# 4_Sensors.net
KiCad netlist of a schematic drawn in Altium Designer
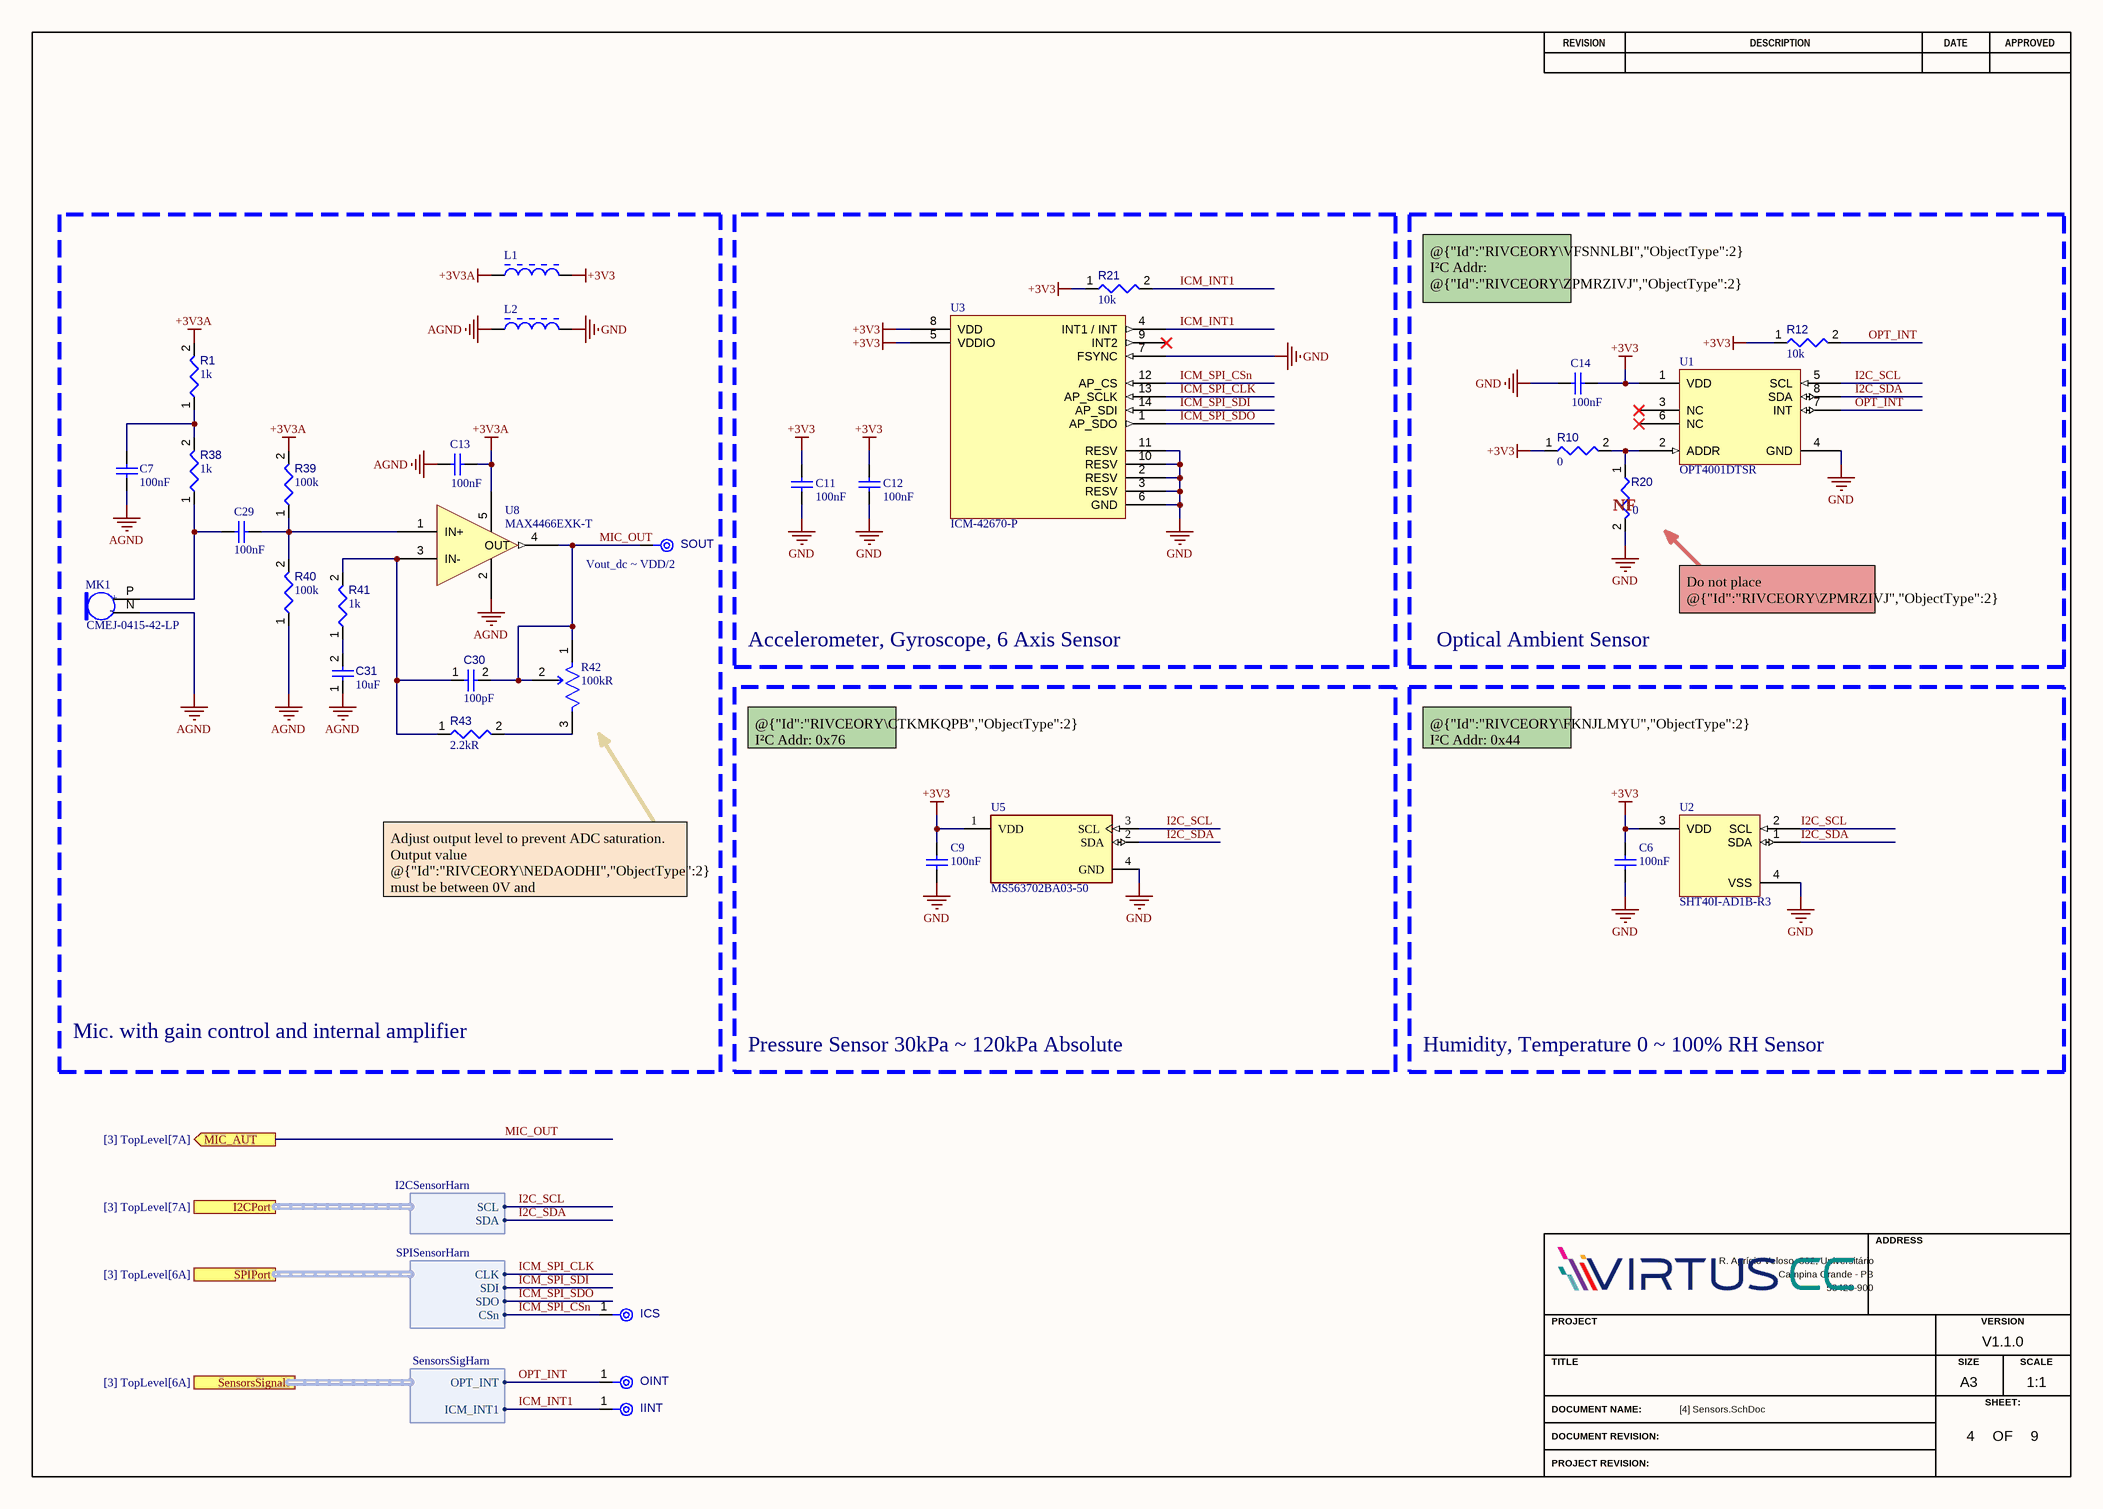
[diagram p0: [4] Sensors.SchDoc]

(export (version "E")
  (design (tool "Eeschema 10.0.6"))
  (components
    (comp (ref "C6")
      (value "100nF")
      (footprint "CAPC0603(1608)100_L")
      (description "Multilayer Ceramic Capacitor, 0.1 uF, 16 V, ± 20%, X7R, 0603 [1608 Metric]")
      (fields (field (name "TOLERANCE") "20%") (field (name "Comment") "VJ0603Y104MXJCW1BC"))
      (libsource (lib "UFCG - Universidade Federal de Campina Grande") (part "CAP"))
    )
    (comp (ref "C7")
      (value "100nF")
      (footprint "CAPC0603(1608)100_L")
      (description "Multilayer Ceramic Capacitor, 0.1 uF, 16 V, ± 20%, X7R, 0603 [1608 Metric]")
      (fields (field (name "TOLERANCE") "20%") (field (name "Comment") "VJ0603Y104MXJCW1BC"))
      (libsource (lib "UFCG - Universidade Federal de Campina Grande") (part "CAP"))
    )
    (comp (ref "C9")
      (value "100nF")
      (footprint "CAPC0603(1608)100_L")
      (description "Multilayer Ceramic Capacitor, 0.1 uF, 16 V, ± 20%, X7R, 0603 [1608 Metric]")
      (fields (field (name "TOLERANCE") "20%") (field (name "Comment") "VJ0603Y104MXJCW1BC"))
      (libsource (lib "UFCG - Universidade Federal de Campina Grande") (part "CAP"))
    )
    (comp (ref "C11")
      (value "100nF")
      (footprint "CAPC0603(1608)100_L")
      (description "Multilayer Ceramic Capacitor, 0.1 uF, 16 V, ± 20%, X7R, 0603 [1608 Metric]")
      (fields (field (name "TOLERANCE") "20%") (field (name "Comment") "VJ0603Y104MXJCW1BC"))
      (libsource (lib "UFCG - Universidade Federal de Campina Grande") (part "CAP"))
    )
    (comp (ref "C12")
      (value "100nF")
      (footprint "CAPC0603(1608)100_L")
      (description "Multilayer Ceramic Capacitor, 0.1 uF, 16 V, ± 20%, X7R, 0603 [1608 Metric]")
      (fields (field (name "TOLERANCE") "20%") (field (name "Comment") "VJ0603Y104MXJCW1BC"))
      (libsource (lib "UFCG - Universidade Federal de Campina Grande") (part "CAP"))
    )
    (comp (ref "C13")
      (value "100nF")
      (footprint "CAPC0603(1608)100_L")
      (description "Multilayer Ceramic Capacitor, 0.1 uF, 16 V, ± 20%, X7R, 0603 [1608 Metric]")
      (fields (field (name "TOLERANCE") "20%") (field (name "Comment") "VJ0603Y104MXJCW1BC"))
      (libsource (lib "UFCG - Universidade Federal de Campina Grande") (part "CAP"))
    )
    (comp (ref "C14")
      (value "100nF")
      (footprint "CAPC0603(1608)100_L")
      (description "Multilayer Ceramic Capacitor, 0.1 uF, 16 V, ± 20%, X7R, 0603 [1608 Metric]")
      (fields (field (name "TOLERANCE") "20%") (field (name "Comment") "VJ0603Y104MXJCW1BC"))
      (libsource (lib "UFCG - Universidade Federal de Campina Grande") (part "CAP"))
    )
    (comp (ref "C29")
      (value "100nF")
      (footprint "CAPC0603(1608)100_L")
      (description "Multilayer Ceramic Capacitor, 0.1 uF, 16 V, ± 20%, X7R, 0603 [1608 Metric]")
      (fields (field (name "TOLERANCE") "20%") (field (name "Comment") "VJ0603Y104MXJCW1BC"))
      (libsource (lib "UFCG - Universidade Federal de Campina Grande") (part "CAP"))
    )
    (comp (ref "C30")
      (value "100pF")
      (footprint "CAPC0603(1608)100_L")
      (description "Multilayer Ceramic Capacitor, 100 pF, 50 V, ï¿½ 10%, C0G (NP0), 0603 [1608 Metric]")
      (fields (field (name "TOLERANCE") "10%") (field (name "Comment") "C0603C101K5GACTU"))
      (libsource (lib "UFCG - Universidade Federal de Campina Grande") (part "CAP-NP-2"))
    )
    (comp (ref "C31")
      (value "10uF")
      (footprint "CAPC0603(1608)100_L")
      (description "Multilayer Ceramic Capacitor, 10 uF, 6.3 V, ± 20%, X5R, 0603 [1608 Metric]")
      (fields (field (name "TOLERANCE") "20%") (field (name "Comment") "GRM188R60J106ME47D"))
      (libsource (lib "UFCG - Universidade Federal de Campina Grande") (part "CAP-NP-2"))
    )
    (comp (ref "ICS")
      (value "TPAD6R")
      (footprint "TP06R")
      (description "0.6mm round")
      (libsource (lib "UFCG - Universidade Federal de Campina Grande") (part "CMP-001-0001-4"))
    )
    (comp (ref "IINT")
      (value "TPAD6R")
      (footprint "TP06R")
      (description "0.6mm round")
      (libsource (lib "UFCG - Universidade Federal de Campina Grande") (part "CMP-001-0001-4"))
    )
    (comp (ref "L1")
      (value "BLM21PG331SN1D")
      (footprint "INDC2013X105X50ML20T20")
      (fields (field (name "TOLERANCE") "25%") (field (name "MANUFACTURER") "Murata"))
      (libsource (lib "UFCG - Universidade Federal de Campina Grande") (part "IND-FB-2"))
    )
    (comp (ref "L2")
      (value "BLM21PG331SN1D")
      (footprint "INDC2013X105X50ML20T20")
      (fields (field (name "TOLERANCE") "25%") (field (name "MANUFACTURER") "Murata"))
      (libsource (lib "UFCG - Universidade Federal de Campina Grande") (part "IND-FB-2"))
    )
    (comp (ref "MK1")
      (value "CMEJ-0415-42-LP")
      (footprint "MIC_CMEJ-0415-42-LP")
      (description "4.0 mm, Omnidirectional, PCB Mount, 2.0 Vdc, Elecret Condenser Microphone")
      (fields (field (name "MF") "{'manufacturer': u'CUI'}"))
      (libsource (lib "UFCG - Universidade Federal de Campina Grande") (part "CMEJ-0415-42-LP"))
    )
    (comp (ref "OINT")
      (value "TPAD6R")
      (footprint "TP06R")
      (description "0.6mm round")
      (libsource (lib "UFCG - Universidade Federal de Campina Grande") (part "CMP-001-0001-4"))
    )
    (comp (ref "R1")
      (value "1k")
      (footprint "RESC0603(1608)_L")
      (description "Chip Resistor, 1 KOhm, +/-1%, 0.1 W, -55 to 155 degC, 0603 (1608 Metric)")
      (fields (field (name "POWER") "100mW") (field (name "TOLERANCE") "1%"))
      (libsource (lib "UFCG - Universidade Federal de Campina Grande") (part "RES-2"))
    )
    (comp (ref "R10")
      (value "0")
      (footprint "RESC0603(1608)_L")
      (description "Chip Resistor, 0 Ohm, 0.1 W, -55 to 155 degC, 0603 (1608 Metric)")
      (fields (field (name "TOLERANCE") "5%") (field (name "POWER") "100mW"))
      (libsource (lib "UFCG - Universidade Federal de Campina Grande") (part "RES-2"))
    )
    (comp (ref "R12")
      (value "10k")
      (footprint "RESC0603(1608)_L")
      (description "Chip Resistor, 10 KOhm, +/- 1%, 01 W, -55 to 155 degC, 0603 (1608 Metric)")
      (fields (field (name "POWER") "100mW") (field (name "TOLERANCE") "1%"))
      (libsource (lib "UFCG - Universidade Federal de Campina Grande") (part "RES-2"))
    )
    (comp (ref "R20")
      (value "0")
      (footprint "RESC0603(1608)_L")
      (description "Chip Resistor, 0 Ohm, 0.1 W, -55 to 155 degC, 0603 (1608 Metric)")
      (fields (field (name "TOLERANCE") "5%") (field (name "POWER") "100mW"))
      (libsource (lib "UFCG - Universidade Federal de Campina Grande") (part "RES-2"))
    )
    (comp (ref "R21")
      (value "10k")
      (footprint "RESC0603(1608)_L")
      (description "Chip Resistor, 10 KOhm, +/- 1%, 01 W, -55 to 155 degC, 0603 (1608 Metric)")
      (fields (field (name "POWER") "100mW") (field (name "TOLERANCE") "1%"))
      (libsource (lib "UFCG - Universidade Federal de Campina Grande") (part "RES-2"))
    )
    (comp (ref "R38")
      (value "1k")
      (footprint "RESC0603(1608)_L")
      (description "Chip Resistor, 1 KOhm, +/-1%, 0.1 W, -55 to 155 degC, 0603 (1608 Metric)")
      (fields (field (name "POWER") "100mW") (field (name "TOLERANCE") "1%"))
      (libsource (lib "UFCG - Universidade Federal de Campina Grande") (part "RES-2"))
    )
    (comp (ref "R39")
      (value "100k")
      (footprint "RESC0603(1608)_L")
      (description "Chip Resistor, 100 KOhm, +/- 1%, 0.1 W, -55 to 155 degC, 0603 (1608 Metric)")
      (fields (field (name "TOLERANCE") "1%") (field (name "POWER") "100mW"))
      (libsource (lib "UFCG - Universidade Federal de Campina Grande") (part "RES-2"))
    )
    (comp (ref "R40")
      (value "100k")
      (footprint "RESC0603(1608)_L")
      (description "Chip Resistor, 100 KOhm, +/- 1%, 0.1 W, -55 to 155 degC, 0603 (1608 Metric)")
      (fields (field (name "TOLERANCE") "1%") (field (name "POWER") "100mW"))
      (libsource (lib "UFCG - Universidade Federal de Campina Grande") (part "RES-2"))
    )
    (comp (ref "R41")
      (value "1k")
      (footprint "RESC0603(1608)_L")
      (description "Chip Resistor, 1 KOhm, +/-1%, 0.1 W, -55 to 155 degC, 0603 (1608 Metric)")
      (fields (field (name "POWER") "100mW") (field (name "TOLERANCE") "1%"))
      (libsource (lib "UFCG - Universidade Federal de Campina Grande") (part "RES-2"))
    )
    (comp (ref "R42")
      (value "100kR")
      (footprint "FP-TC33X-2-MFG")
      (description "Cermet trimmer potentiometer, 100 kΩ, 0.1 W, SMD, on top, TC33X-2-104E")
      (fields (field (name "TOLERANCE") "25%") (field (name "Comment") "TC33X-2-104E"))
      (libsource (lib "UFCG - Universidade Federal de Campina Grande") (part "13357d81287629c2fd191d242cfa50c"))
    )
    (comp (ref "R43")
      (value "2.2kR")
      (footprint "RESC0603(1608)_L")
      (description "SMD Chip Resistor, 2.2 kOhm, ± 1%, 100 mW, 0603 [1608 Metric], Thick Film, General Purpose")
      (fields (field (name "TOLERANCE") "1%") (field (name "Comment") "CRCW06032K20FKEA"))
      (libsource (lib "UFCG - Universidade Federal de Campina Grande") (part "RES-2"))
    )
    (comp (ref "SOUT")
      (value "TPAD6R")
      (footprint "TP06R")
      (description "0.6mm round")
      (libsource (lib "") (part "CMP-001-0001-4_1"))
    )
    (comp (ref "U1")
      (value "OPT4001DTSR")
      (footprint "SON50P130X60-8N")
      (description "High-speed high-precision digital ambient light sensor (ALS) 8-SOT-5X3 -40 to 85")
      (libsource (lib "UFCG - Universidade Federal de Campina Grande") (part "New symbol 1"))
    )
    (comp (ref "U2")
      (value "SHT40I-AD1B-R3")
      (footprint "QFN80P150X150X55-4N")
      (description "Humidity And Temperature Sensor")
      (libsource (lib "UFCG - Universidade Federal de Campina Grande") (part "SHT40I-AD1B-R3"))
    )
    (comp (ref "U3")
      (value "ICM-42670-P")
      (footprint "QFN50P300X250X81-14N")
      (description "Mems Module, 1.71-3.6 V, Lga-14 Rohs Compliant: Yes")
      (libsource (lib "UFCG - Universidade Federal de Campina Grande") (part "ICM-42670-P"))
    )
    (comp (ref "U5")
      (value "MS563702BA03-50")
      (footprint "FP-MS563702BA03-50-MFG")
      (description "Pressure Sensor, Barometric, 300 mbar, 1200 mbar, QFN, 8, -40 C")
      (libsource (lib "UFCG - Universidade Federal de Campina Grande") (part "74709a9a55dd6d6ee219151e6d8b12f"))
    )
    (comp (ref "U8")
      (value "MAX4466EXK-T")
      (footprint "SOT65P200X110-5N")
      (description "Audio Amp Microphone 1-CH Mono Class-AB 5-Pin SC-70 T/R")
      (libsource (lib "UFCG - Universidade Federal de Campina Grande") (part "MAX4466EXK-T"))
    )
  )
  (nets
    (net (code "4") (name "+3V3") (class "Default")
      (node (ref "C11") (pin "2") (pinfunction "2_2") (pintype "passive"))
      (node (ref "C12") (pin "2") (pinfunction "2_2") (pintype "passive"))
      (node (ref "C14") (pin "1") (pinfunction "1_1") (pintype "passive"))
      (node (ref "C6") (pin "1") (pinfunction "1_1") (pintype "passive"))
      (node (ref "C9") (pin "1") (pinfunction "1_1") (pintype "passive"))
      (node (ref "L1") (pin "2") (pinfunction "2_2") (pintype "passive"))
      (node (ref "R10") (pin "1") (pinfunction "1_1") (pintype "passive"))
      (node (ref "R12") (pin "1") (pinfunction "1_1") (pintype "passive"))
      (node (ref "R21") (pin "1") (pinfunction "1_1") (pintype "passive"))
      (node (ref "U1") (pin "1") (pinfunction "VDD_1") (pintype "power_in"))
      (node (ref "U2") (pin "3") (pinfunction "VDD_3") (pintype "power_in"))
      (node (ref "U3") (pin "5") (pinfunction "VDDIO_5") (pintype "power_in"))
      (node (ref "U3") (pin "8") (pinfunction "VDD_8") (pintype "power_in"))
      (node (ref "U5") (pin "1") (pinfunction "VDD_1") (pintype "power_in"))
    )
    (net (code "5") (name "+3V3A") (class "Default")
      (node (ref "C13") (pin "1") (pinfunction "1_1") (pintype "passive"))
      (node (ref "L1") (pin "1") (pinfunction "1_1") (pintype "passive"))
      (node (ref "R1") (pin "2") (pinfunction "2_2") (pintype "passive"))
      (node (ref "R39") (pin "2") (pinfunction "2_2") (pintype "passive"))
      (node (ref "U8") (pin "5") (pinfunction "VCC_5") (pintype "power_in"))
    )
    (net (code "6") (name "/I2C_SCL") (class "Default")
      (node (ref "U1") (pin "5") (pinfunction "SCL_5") (pintype "input"))
      (node (ref "U2") (pin "2") (pinfunction "SCL_2") (pintype "input"))
      (node (ref "U5") (pin "3") (pinfunction "SCL_3") (pintype "input"))
    )
    (net (code "7") (name "/I2C_SDA") (class "Default")
      (node (ref "U1") (pin "8") (pinfunction "SDA_8") (pintype "bidirectional"))
      (node (ref "U2") (pin "1") (pinfunction "SDA_1") (pintype "bidirectional"))
      (node (ref "U5") (pin "2") (pinfunction "SDA_2") (pintype "bidirectional"))
    )
    (net (code "8") (name "/ICM_INT1") (class "Default")
      (node (ref "IINT") (pin "1") (pinfunction "TP_1") (pintype "passive"))
      (node (ref "R21") (pin "2") (pinfunction "2_2") (pintype "passive"))
      (node (ref "U3") (pin "4") (pinfunction "INT1_/_INT_4") (pintype "output"))
    )
    (net (code "9") (name "/ICM_SPI_CLK") (class "Default")
      (node (ref "U3") (pin "13") (pinfunction "AP_SCLK_13") (pintype "input"))
    )
    (net (code "10") (name "/ICM_SPI_CSn") (class "Default")
      (node (ref "ICS") (pin "1") (pinfunction "TP_1") (pintype "passive"))
      (node (ref "U3") (pin "12") (pinfunction "AP_CS_12") (pintype "input"))
    )
    (net (code "11") (name "/ICM_SPI_SDI") (class "Default")
      (node (ref "U3") (pin "14") (pinfunction "AP_SDI_14") (pintype "input"))
    )
    (net (code "12") (name "/ICM_SPI_SDO") (class "Default")
      (node (ref "U3") (pin "1") (pinfunction "AP_SDO_1") (pintype "output"))
    )
    (net (code "13") (name "/MIC_OUT") (class "Default")
      (node (ref "C30") (pin "2") (pinfunction "2_2") (pintype "passive"))
      (node (ref "R42") (pin "1") (pinfunction "CCW_1") (pintype "passive"))
      (node (ref "R42") (pin "2") (pinfunction "WIPER_2") (pintype "passive"))
      (node (ref "SOUT") (pin "1") (pinfunction "TP_1") (pintype "passive"))
      (node (ref "U8") (pin "4") (pinfunction "OUT_4") (pintype "output"))
    )
    (net (code "14") (name "/OPT_INT") (class "Default")
      (node (ref "OINT") (pin "1") (pinfunction "TP_1") (pintype "passive"))
      (node (ref "R12") (pin "2") (pinfunction "2_2") (pintype "passive"))
      (node (ref "U1") (pin "7") (pinfunction "INT_7") (pintype "bidirectional"))
    )
    (net (code "18") (name "AGND") (class "Default")
      (node (ref "C13") (pin "2") (pinfunction "2_2") (pintype "passive"))
      (node (ref "C31") (pin "1") (pinfunction "1_1") (pintype "passive"))
      (node (ref "C7") (pin "1") (pinfunction "1_1") (pintype "passive"))
      (node (ref "L2") (pin "1") (pinfunction "1_1") (pintype "passive"))
      (node (ref "MK1") (pin "N") (pinfunction "GND_N") (pintype "passive"))
      (node (ref "R40") (pin "1") (pinfunction "1_1") (pintype "passive"))
      (node (ref "U8") (pin "2") (pinfunction "GND_2") (pintype "power_in"))
    )
    (net (code "19") (name "GND") (class "Default")
      (node (ref "C11") (pin "1") (pinfunction "1_1") (pintype "passive"))
      (node (ref "C12") (pin "1") (pinfunction "1_1") (pintype "passive"))
      (node (ref "C14") (pin "2") (pinfunction "2_2") (pintype "passive"))
      (node (ref "C6") (pin "2") (pinfunction "2_2") (pintype "passive"))
      (node (ref "C9") (pin "2") (pinfunction "2_2") (pintype "passive"))
      (node (ref "L2") (pin "2") (pinfunction "2_2") (pintype "passive"))
      (node (ref "R20") (pin "2") (pinfunction "2_2") (pintype "passive"))
      (node (ref "U1") (pin "4") (pinfunction "GND_4") (pintype "power_in"))
      (node (ref "U2") (pin "4") (pinfunction "VSS_4") (pintype "power_in"))
      (node (ref "U3") (pin "10") (pinfunction "RESV_10") (pintype "passive"))
      (node (ref "U3") (pin "11") (pinfunction "RESV_11") (pintype "passive"))
      (node (ref "U3") (pin "2") (pinfunction "RESV_2") (pintype "passive"))
      (node (ref "U3") (pin "3") (pinfunction "RESV_3") (pintype "passive"))
      (node (ref "U3") (pin "6") (pinfunction "GND_6") (pintype "power_in"))
      (node (ref "U3") (pin "7") (pinfunction "FSYNC_7") (pintype "input"))
      (node (ref "U5") (pin "4") (pinfunction "GND_4") (pintype "power_in"))
    )
    (net (code "20") (name "Net-(C7-Pad2)") (class "Default")
      (node (ref "C7") (pin "2") (pinfunction "2_2") (pintype "passive"))
      (node (ref "R1") (pin "1") (pinfunction "1_1") (pintype "passive"))
      (node (ref "R38") (pin "2") (pinfunction "2_2") (pintype "passive"))
    )
    (net (code "21") (name "Net-(C31-Pad2)") (class "Default")
      (node (ref "C31") (pin "2") (pinfunction "2_2") (pintype "passive"))
      (node (ref "R41") (pin "1") (pinfunction "1_1") (pintype "passive"))
    )
    (net (code "22") (name "Net-(MK1-OUTPUT)") (class "Default")
      (node (ref "C29") (pin "2") (pinfunction "2_2") (pintype "passive"))
      (node (ref "MK1") (pin "P") (pinfunction "OUTPUT_P") (pintype "passive"))
      (node (ref "R38") (pin "1") (pinfunction "1_1") (pintype "passive"))
    )
    (net (code "23") (name "Net-(R42-CW)") (class "Default")
      (node (ref "R42") (pin "3") (pinfunction "CW_3") (pintype "passive"))
      (node (ref "R43") (pin "2") (pinfunction "2_2") (pintype "passive"))
    )
    (net (code "24") (name "Net-(U1-ADDR)") (class "Default")
      (node (ref "R10") (pin "2") (pinfunction "2_2") (pintype "passive"))
      (node (ref "R20") (pin "1") (pinfunction "1_1") (pintype "passive"))
      (node (ref "U1") (pin "2") (pinfunction "ADDR_2") (pintype "input"))
    )
    (net (code "25") (name "Net-(U8-IN+)") (class "Default")
      (node (ref "C29") (pin "1") (pinfunction "1_1") (pintype "passive"))
      (node (ref "R39") (pin "1") (pinfunction "1_1") (pintype "passive"))
      (node (ref "R40") (pin "2") (pinfunction "2_2") (pintype "passive"))
      (node (ref "U8") (pin "1") (pinfunction "IN+_1") (pintype "passive"))
    )
    (net (code "26") (name "Net-(U8-IN-)") (class "Default")
      (node (ref "C30") (pin "1") (pinfunction "1_1") (pintype "passive"))
      (node (ref "R41") (pin "2") (pinfunction "2_2") (pintype "passive"))
      (node (ref "R43") (pin "1") (pinfunction "1_1") (pintype "passive"))
      (node (ref "U8") (pin "3") (pinfunction "IN-_3") (pintype "passive"))
    )
    (net (code "27") (name "unconnected-(U1-NC-Pad3)") (class "Default")
      (node (ref "U1") (pin "3") (pinfunction "NC_3") (pintype "passive+no_connect"))
    )
    (net (code "28") (name "unconnected-(U1-NC-Pad6)") (class "Default")
      (node (ref "U1") (pin "6") (pinfunction "NC_6") (pintype "passive+no_connect"))
    )
    (net (code "29") (name "unconnected-(U3-INT2-Pad9)") (class "Default")
      (node (ref "U3") (pin "9") (pinfunction "INT2_9") (pintype "output+no_connect"))
    )
  )
)
